# Relay.net
KiCad netlist of a schematic drawn in Altium Designer
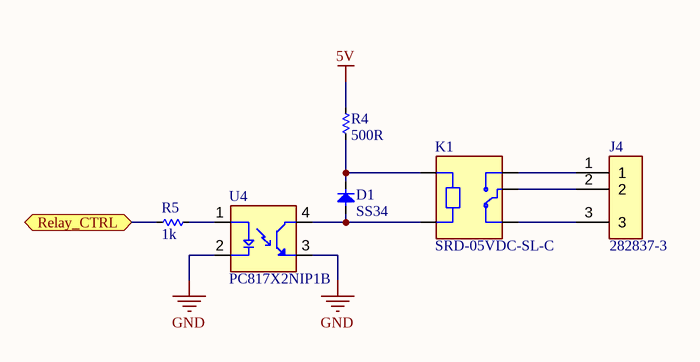
[diagram p0: Relay.SchDoc]

(export (version "E")
  (design (tool "Eeschema 10.0.6"))
  (components
    (comp (ref "D1")
      (value "SS34")
      (footprint "DO-214AC_SMA")
      (description "Default Diode")
      (fields (field (name "PUBLISHER") "Altium Limited"))
      (libsource (lib "BTL_SCHLIB") (part "Diode SMD"))
    )
    (comp (ref "J4")
      (value "282837-3")
      (footprint "TE_282837-3")
      (description "TERMI-BLOK PCB MOUNT 3P")
      (libsource (lib "BTL_SCHLIB") (part "282837-3"))
    )
    (comp (ref "K1")
      (value "SRD-05VDC-SL-C")
      (footprint "RELAY_SRD-05VDC-SL-C")
      (fields (field (name "MF") "Songle Relay"))
      (libsource (lib "BTL_SCHLIB") (part "SRD-05VDC-SL-C"))
    )
    (comp (ref "R4")
      (value "500R")
      (footprint "RES_C_1608X60")
      (description "RES")
      (libsource (lib "BTL_SCHLIB") (part "RES_SMD"))
    )
    (comp (ref "R5")
      (value "1k")
      (footprint "RES_C_1608X60")
      (description "RES")
      (libsource (lib "BTL_SCHLIB") (part "RES_SMD"))
    )
    (comp (ref "U4")
      (value "PC817X2NIP1B")
      (footprint "SOIC254P960X420-4N")
      (description "Optocoupler DC-IN 1-CH Transistor DC-OUT 4-Pin DIP SMD T/R")
      (fields (field (name "MF") "Sharp Microelectronics"))
      (libsource (lib "BTL_SCHLIB") (part "PC817X2NIP1B"))
    )
  )
  (nets
    (net (code "1") (name "/Relay_CTRL") (class "Default")
      (node (ref "R5") (pin "1") (pinfunction "1_1") (pintype "passive"))
    )
    (net (code "2") (name "5V") (class "Default")
      (node (ref "R4") (pin "2") (pinfunction "2_2") (pintype "passive"))
    )
    (net (code "3") (name "GND") (class "Default")
      (node (ref "U4") (pin "2") (pinfunction "C_2") (pintype "passive"))
      (node (ref "U4") (pin "3") (pinfunction "ET_3") (pintype "passive"))
    )
    (net (code "4") (name "Net-(D1-A)") (class "Default")
      (node (ref "D1") (pin "2") (pinfunction "A_2") (pintype "passive"))
      (node (ref "K1") (pin "A2") (pinfunction "A2_A2") (pintype "passive"))
      (node (ref "U4") (pin "4") (pinfunction "CT_4") (pintype "passive"))
    )
    (net (code "5") (name "Net-(D1-K)") (class "Default")
      (node (ref "D1") (pin "1") (pinfunction "K_1") (pintype "passive"))
      (node (ref "K1") (pin "A1") (pinfunction "A1_A1") (pintype "passive"))
      (node (ref "R4") (pin "1") (pinfunction "1_1") (pintype "passive"))
    )
    (net (code "6") (name "Net-(J4-Pad1)") (class "Default")
      (node (ref "J4") (pin "1") (pinfunction "1_1") (pintype "passive"))
      (node (ref "K1") (pin "NO") (pinfunction "NO_NO") (pintype "passive"))
    )
    (net (code "7") (name "Net-(J4-Pad2)") (class "Default")
      (node (ref "J4") (pin "2") (pinfunction "2_2") (pintype "passive"))
      (node (ref "K1") (pin "COM") (pinfunction "COM_COM") (pintype "passive"))
    )
    (net (code "8") (name "Net-(J4-Pad3)") (class "Default")
      (node (ref "J4") (pin "3") (pinfunction "3_3") (pintype "passive"))
      (node (ref "K1") (pin "NC") (pinfunction "NC_NC") (pintype "passive"))
    )
    (net (code "9") (name "Net-(U4-A)") (class "Default")
      (node (ref "R5") (pin "2") (pinfunction "2_2") (pintype "passive"))
      (node (ref "U4") (pin "1") (pinfunction "A_1") (pintype "passive"))
    )
  )
)
